# Schematic_Rev1.net
KiCad netlist of a schematic drawn in Altium Designer
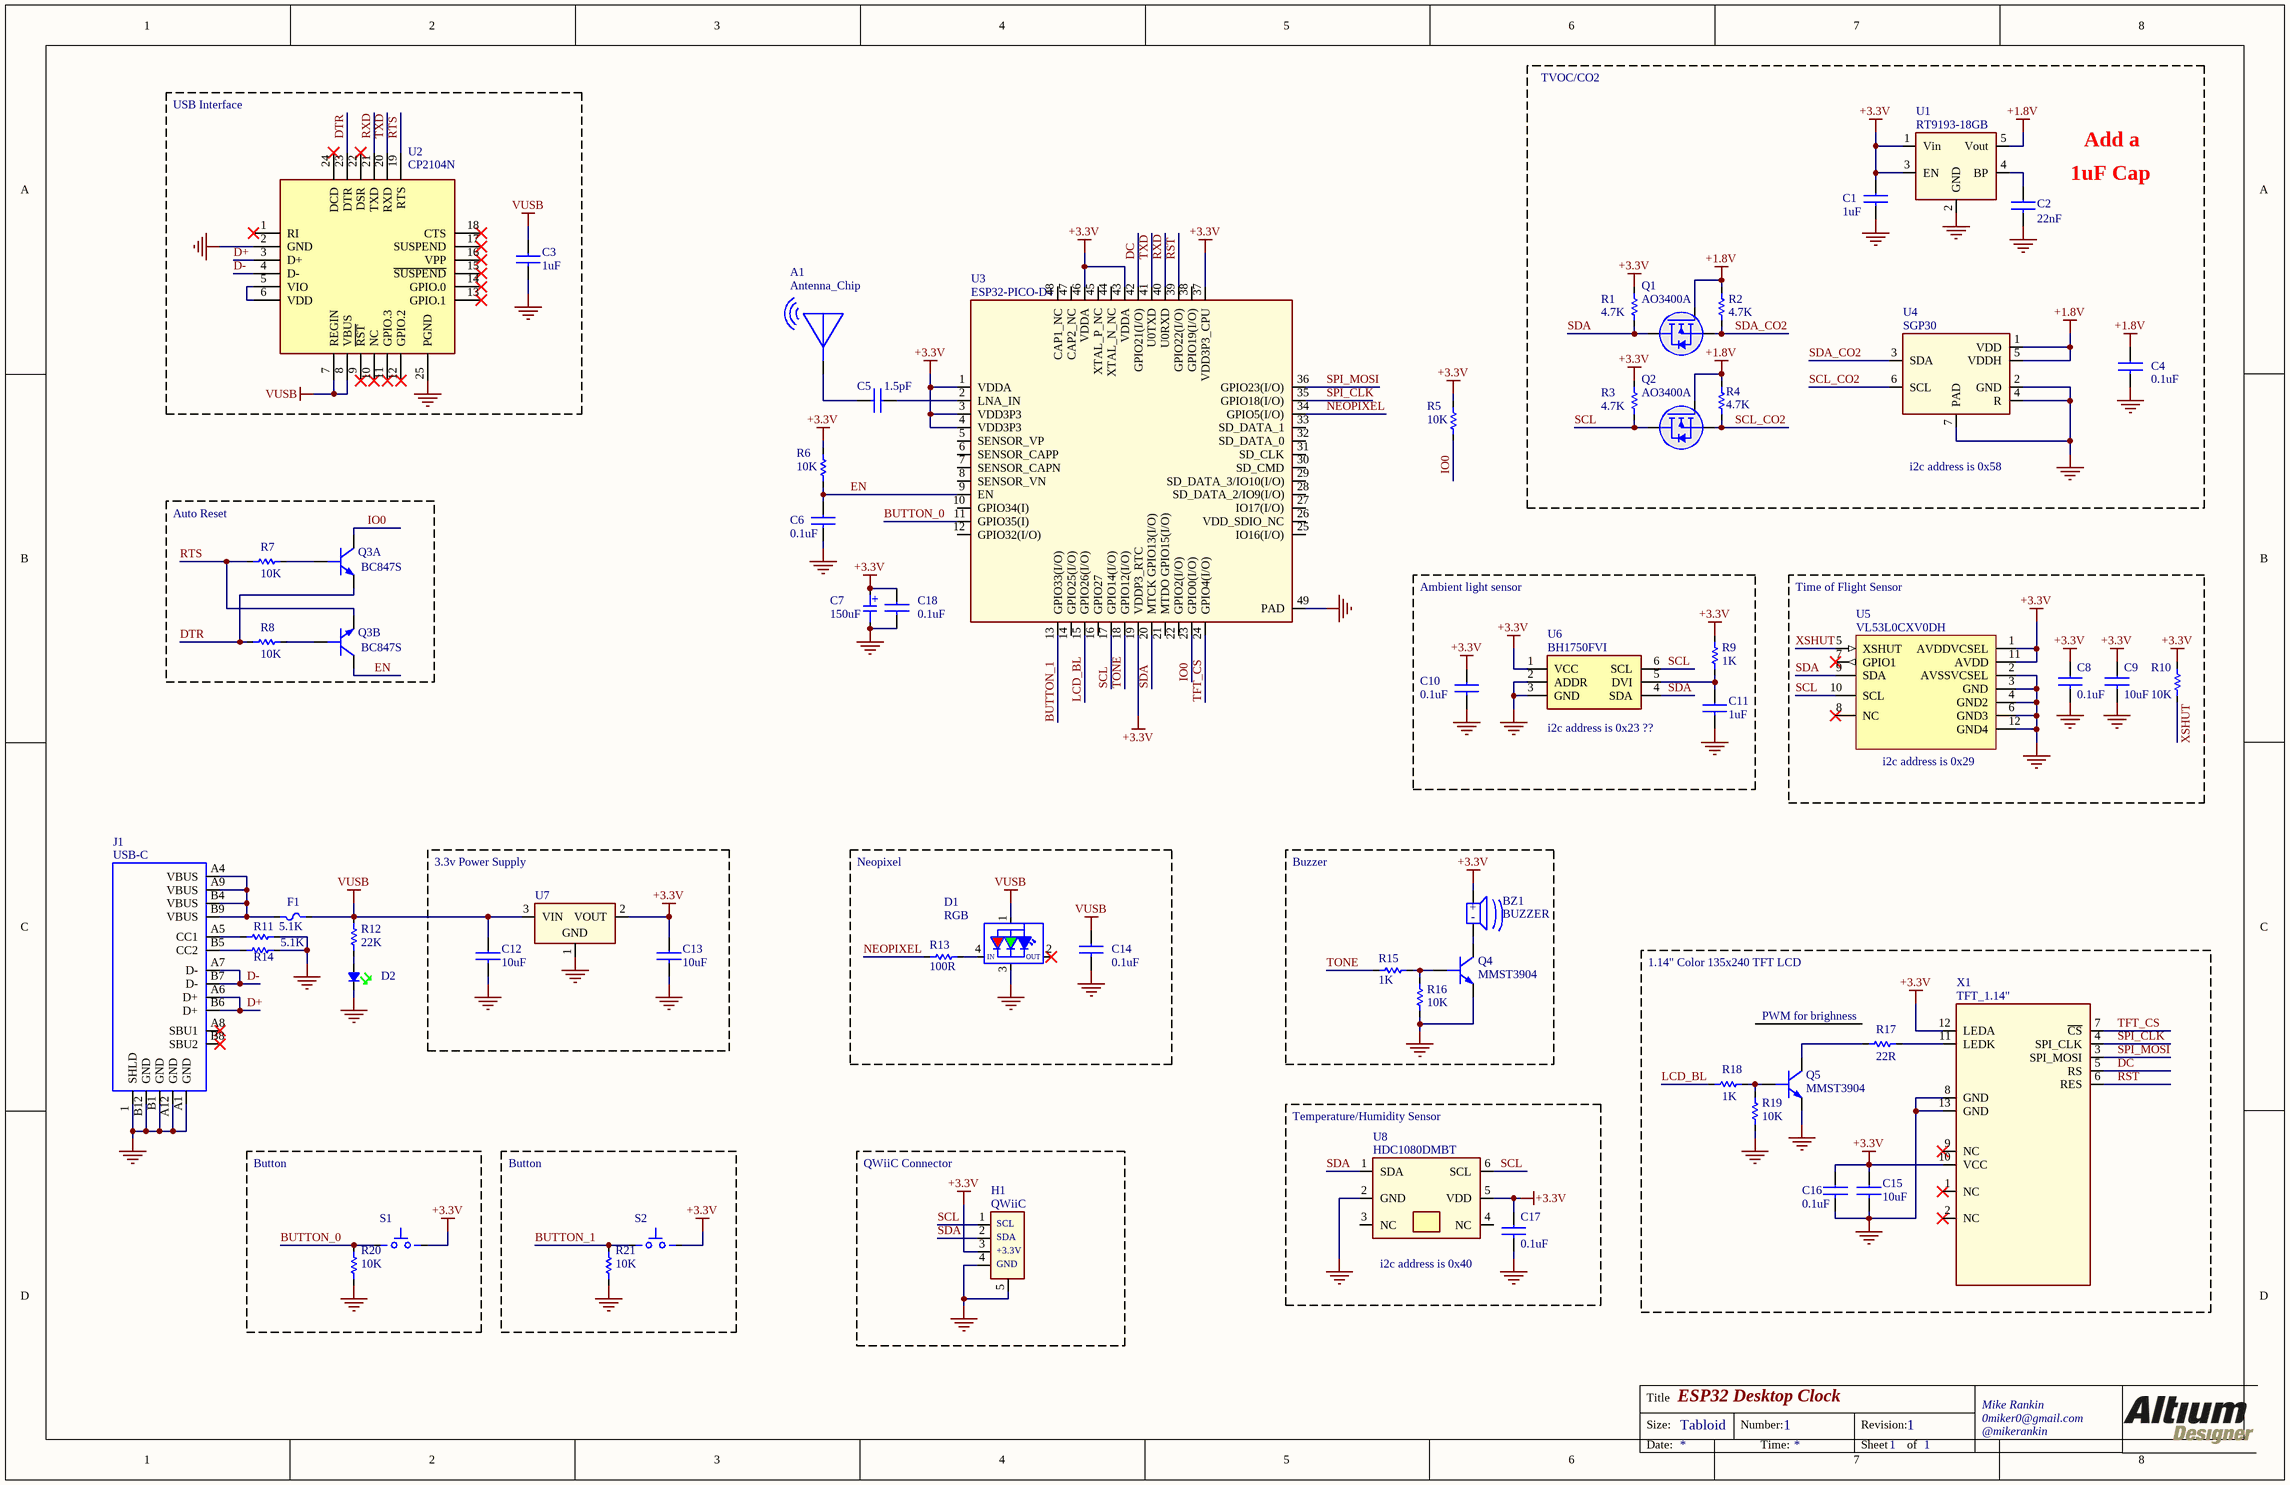
[diagram p0: Schematic_Rev1.SchDoc]

(export (version "E")
  (design (tool "Eeschema 10.0.6"))
  (components
    (comp (ref "A1")
      (value "Antenna_Chip")
      (footprint "AN9520-245")
      (description "Antenna Chip 2.4Gig")
      (fields (field (name "MANUFACTURER") "Rainsun") (field (name "PART_NUMBER") "C99665"))
      (libsource (lib "MAR") (part "Antenna_Chip"))
    )
    (comp (ref "BZ1")
      (value "BUZZER")
      (footprint "ST-025BH")
      (description "BUZZER MAGNETIC 2.7kHz Tone 2-4V SMD")
      (fields (field (name "PART_NUMBER") "ST-025BH") (field (name "MANUFACTURER") "SOBERTON"))
      (libsource (lib "MAR") (part "Buzzer_SMT"))
    )
    (comp (ref "C1")
      (value "1uF")
      (footprint "CAPC1005X56N")
      (description "CAP 1uF 0402")
      (libsource (lib "MAR") (part "CAP_0402"))
    )
    (comp (ref "C2")
      (value "22nF")
      (footprint "CAPC1005X56N")
      (description "CAP 22nF 0402")
      (libsource (lib "MAR") (part "CAP_0402"))
    )
    (comp (ref "C3")
      (value "1uF")
      (footprint "CAPC1005X56N")
      (description "CAP 1uF 16V 0402")
      (fields (field (name "PARTNUMBER") "C83063") (field (name "MANUFACTURER") "Walsin"))
      (libsource (lib "MAR") (part "CAP_0603"))
    )
    (comp (ref "C4")
      (value "0.1uF")
      (footprint "CAPC1005X56N")
      (description "CAP 0.1uF 0402")
      (libsource (lib "MAR") (part "CAP_0402"))
    )
    (comp (ref "C5")
      (value "1.5pF")
      (footprint "CAPC1005X56N")
      (description "CAP 1.5pF 0402")
      (fields (field (name "PART_NUMBER") "C147344") (field (name "MANUFACTURER") "Dafron"))
      (libsource (lib "MAR") (part "CAP_0402"))
    )
    (comp (ref "C6")
      (value "0.1uF")
      (footprint "CAPC1005X56N")
      (description "CAP 0.1uF 0402")
      (fields (field (name "PARTNUMBER") "C344190") (field (name "MANUFACTURER") "CCTC"))
      (libsource (lib "MAR") (part "CAP_0402"))
    )
    (comp (ref "C7")
      (value "150uF")
      (footprint "CAP_SM_CAN_0.250_DIA")
      (description "CAP 150uF, 10V SMT")
      (fields (field (name "PART_NUMBER") "C242018") (field (name "MANUFACTURER") "Suncon"))
      (libsource (lib "MAR") (part "CAP_ELEC_SMT"))
    )
    (comp (ref "C8")
      (value "0.1uF")
      (footprint "CAPC1005X56N")
      (description "CAP 0.1uF 0402")
      (fields (field (name "PARTNUMBER") "C344190") (field (name "MANUFACTURER") "CCTC"))
      (libsource (lib "MAR") (part "CAP_0402"))
    )
    (comp (ref "C9")
      (value "10uF")
      (footprint "CAPC2012X140N")
      (description "CAP 10uF 0805")
      (fields (field (name "MANUFACTURER") "Samsung") (field (name "PARTNUMBER") "C307520"))
      (libsource (lib "MAR") (part "CAP_0805"))
    )
    (comp (ref "C10")
      (value "0.1uF")
      (footprint "CAPC1005X56N")
      (description "CAP 0.1uF 0402")
      (libsource (lib "MAR") (part "CAP_0402"))
    )
    (comp (ref "C11")
      (value "1uF")
      (footprint "CAPC1005X56N")
      (description "CAP 1uF 16V 0402")
      (fields (field (name "PARTNUMBER") "C83063") (field (name "MANUFACTURER") "Walsin"))
      (libsource (lib "MAR") (part "CAP_0603"))
    )
    (comp (ref "C12")
      (value "10uF")
      (footprint "CAPC2012X140N")
      (description "CAP 10uF 16V 0805")
      (fields (field (name "PARTNUMBER") "C162317") (field (name "MANUFACTURER") "Murata"))
      (libsource (lib "MAR") (part "CAP_0805"))
    )
    (comp (ref "C13")
      (value "10uF")
      (footprint "CAPC2012X140N")
      (description "CAP 10uF 16V 0805")
      (fields (field (name "PARTNUMBER") "C162317") (field (name "MANUFACTURER") "Murata"))
      (libsource (lib "MAR") (part "CAP_0805"))
    )
    (comp (ref "C14")
      (value "0.1uF")
      (footprint "CAPC1005X56N")
      (description "CAP 0.1uF 0402")
      (libsource (lib "MAR") (part "CAP_0402"))
    )
    (comp (ref "C15")
      (value "10uF")
      (footprint "CAPC2012X140N")
      (description "CAP 10uF 0805")
      (fields (field (name "MANUFACTURER") "Samsung") (field (name "PARTNUMBER") "C307520"))
      (libsource (lib "MAR") (part "CAP_0805"))
    )
    (comp (ref "C16")
      (value "0.1uF")
      (footprint "CAPC1005X56N")
      (description "CAP 0.1uF 0402")
      (fields (field (name "PARTNUMBER") "C344190") (field (name "MANUFACTURER") "CCTC"))
      (libsource (lib "MAR") (part "CAP_0402"))
    )
    (comp (ref "C17")
      (value "0.1uF")
      (footprint "CAPC1005X56N")
      (description "CAP 0.1uF 0402")
      (fields (field (name "PARTNUMBER") "C344190") (field (name "MANUFACTURER") "CCTC"))
      (libsource (lib "MAR") (part "CAP_0402"))
    )
    (comp (ref "C18")
      (value "0.1uF")
      (footprint "CAPC1005X56N")
      (description "CAP 0.1uF 0402")
      (libsource (lib "MAR") (part "CAP_0402"))
    )
    (comp (ref "D1")
      (value "RGB")
      (footprint "SMD-5050")
      (description "LED,RGB,NEOPIXEL,WS2818")
      (fields (field (name "PART_NUMBER") "C139127") (field (name "MANUFACTURER") "Worldsemi"))
      (libsource (lib "MAR") (part "WS2812"))
    )
    (comp (ref "D2")
      (value "Green Led")
      (footprint "LED1005X40N-Green")
      (description "LED Green 0402")
      (fields (field (name "PART_NUMBER") "C74338"))
      (libsource (lib "MAR") (part "LED_0402_SMALL_GREEN"))
    )
    (comp (ref "F1")
      (value "TLC-PSMD050")
      (footprint "PTC2012X70L")
      (description "PTC FUSE 500mA hold, 1A trip 0805 SMD")
      (fields (field (name "MANUFACTURER") "TLC") (field (name "LCSC_PART_NUMBER") "C261942"))
      (libsource (lib "MAR") (part "PTC_FUSE"))
    )
    (comp (ref "H1")
      (value "QWiiC")
      (footprint "SM04B-SRSS-TB")
      (description "CONN HEADER 4POS .100 R/A QWIIC")
      (fields (field (name "MANUFACTURER") "JST") (field (name "PARTNUMBER") "SM04B-SRSS-TB(LF)(SN)"))
      (libsource (lib "MAR") (part "SM04B-SRSS-TB"))
    )
    (comp (ref "J1")
      (value "USB-C")
      (footprint "TYPE-C-31-M-12")
      (description "CONN RECPT USB-C")
      (fields (field (name "MANUFACTURER") "KHE") (field (name "PART_NUMBER") "C165948"))
      (libsource (lib "MAR") (part "USB-C"))
    )
    (comp (ref "Q1")
      (value "~")
      (footprint "SOT95P240X110-3N")
      (description "MOSFET N-CH 30V 35.7A SOT-23")
      (fields (field (name "MANUFACTURER") "Alpha & Omega") (field (name "PARTNUMBER") "AO3400A"))
      (libsource (lib "MAR") (part "AO3400A"))
    )
    (comp (ref "Q2")
      (value "~")
      (footprint "SOT95P240X110-3N")
      (description "MOSFET N-CH 30V 35.7A SOT-23")
      (fields (field (name "MANUFACTURER") "Alpha & Omega") (field (name "PARTNUMBER") "AO3400A"))
      (libsource (lib "MAR") (part "AO3400A"))
    )
    (comp (ref "Q3")
      (value "BC847S")
      (footprint "SOT65P210X110-6N")
      (description "TRANS 2NPN 44V 0.1A SC-70-6")
      (fields (field (name "MANUFACTURER") "Changjiang") (field (name "PARTNUMBER") "BC847S"))
      (libsource (lib "MAR") (part "BC847S"))
    )
    (comp (ref "Q4")
      (value "MMST3904")
      (footprint "SC-70")
      (description "TRANSISTOR NPN GP 40V SC-70")
      (fields (field (name "MANUFACTURER") "Changjiang") (field (name "PART_NUMBER") "C54879"))
      (libsource (lib "MAR") (part "MMST3904"))
    )
    (comp (ref "Q5")
      (value "MMST3904")
      (footprint "SC-70")
      (description "TRANSISTOR NPN GP 40V SC-70")
      (fields (field (name "MANUFACTURER") "Changjiang") (field (name "PART_NUMBER") "C54879"))
      (libsource (lib "MAR") (part "MMST3904"))
    )
    (comp (ref "R1")
      (value "4.7K")
      (footprint "RESC1005X40L (0402 FOOTPRINT)")
      (description "RES 4.7K 0402")
      (libsource (lib "MAR") (part "RES_0402"))
    )
    (comp (ref "R2")
      (value "4.7K")
      (footprint "RESC1005X40L (0402 FOOTPRINT)")
      (description "RES 4.7K 0402")
      (libsource (lib "MAR") (part "RES_0402"))
    )
    (comp (ref "R3")
      (value "4.7K")
      (footprint "RESC1005X40L (0402 FOOTPRINT)")
      (description "RES 4.7K 0402")
      (libsource (lib "MAR") (part "RES_0402"))
    )
    (comp (ref "R4")
      (value "4.7K")
      (footprint "RESC1005X40L (0402 FOOTPRINT)")
      (description "RES 4.7K 0402")
      (libsource (lib "MAR") (part "RES_0402"))
    )
    (comp (ref "R5")
      (value "10K")
      (footprint "RESC1005X40L (0402 FOOTPRINT)")
      (description "RES 10K 0402")
      (fields (field (name "PARTNUMBER") "C258091") (field (name "MANUFACTURER") "Guangdong"))
      (libsource (lib "MAR") (part "RES_0402"))
    )
    (comp (ref "R6")
      (value "10K")
      (footprint "RESC1005X40L (0402 FOOTPRINT)")
      (description "RES 10K 0402")
      (fields (field (name "PARTNUMBER") "C258091") (field (name "MANUFACTURER") "Guangdong"))
      (libsource (lib "MAR") (part "RES_0402"))
    )
    (comp (ref "R7")
      (value "10K")
      (footprint "RESC1005X40L (0402 FOOTPRINT)")
      (description "RES 10K 0402")
      (fields (field (name "PARTNUMBER") "C258091") (field (name "MANUFACTURER") "Guangdong"))
      (libsource (lib "MAR") (part "RES_0402"))
    )
    (comp (ref "R8")
      (value "10K")
      (footprint "RESC1005X40L (0402 FOOTPRINT)")
      (description "RES 10K 0402")
      (fields (field (name "PARTNUMBER") "C258091") (field (name "MANUFACTURER") "Guangdong"))
      (libsource (lib "MAR") (part "RES_0402"))
    )
    (comp (ref "R9")
      (value "1K")
      (footprint "RESC1005X40L (0402 FOOTPRINT)")
      (description "RES 1K 0402")
      (fields (field (name "PARTNUMBER") "C106235") (field (name "MANUFACTURER") "Yageo"))
      (libsource (lib "MAR") (part "RES_0402"))
    )
    (comp (ref "R10")
      (value "10K")
      (footprint "RESC1005X40L (0402 FOOTPRINT)")
      (description "RES 10K 0402")
      (fields (field (name "PARTNUMBER") "C258091") (field (name "MANUFACTURER") "Guangdong"))
      (libsource (lib "MAR") (part "RES_0402"))
    )
    (comp (ref "R11")
      (value "5.1K")
      (footprint "RESC1005X40L (0402 FOOTPRINT)")
      (description "RES 5.1K 0402")
      (libsource (lib "MAR") (part "RES_0603"))
    )
    (comp (ref "R12")
      (value "22K")
      (footprint "RESC1005X40L (0402 FOOTPRINT)")
      (description "RES 22K 0402")
      (fields (field (name "MANUFACTURER") "LIZ Elec") (field (name "PARTNUMBER") "C100310"))
      (libsource (lib "MAR") (part "RES_0603"))
    )
    (comp (ref "R13")
      (value "100R")
      (footprint "RESC1005X40L (0402 FOOTPRINT)")
      (description "RES 100R 0402")
      (fields (field (name "MANUFACTURER") "Yageo") (field (name "LCSC_PART_NUMBER") "C106232"))
      (libsource (lib "MAR") (part "RES_0603"))
    )
    (comp (ref "R14")
      (value "5.1K")
      (footprint "RESC1005X40L (0402 FOOTPRINT)")
      (description "RES 5.1K 0402")
      (libsource (lib "MAR") (part "RES_0603"))
    )
    (comp (ref "R15")
      (value "1K")
      (footprint "RESC1005X40L (0402 FOOTPRINT)")
      (description "RES 1K 0402")
      (libsource (lib "MAR") (part "RES_0402"))
    )
    (comp (ref "R16")
      (value "10K")
      (footprint "RESC1005X40L (0402 FOOTPRINT)")
      (description "RES 10K 0402")
      (fields (field (name "PARTNUMBER") "C258091") (field (name "MANUFACTURER") "Guangdong"))
      (libsource (lib "MAR") (part "RES_0402"))
    )
    (comp (ref "R17")
      (value "22R")
      (footprint "RESC1005X40L (0402 FOOTPRINT)")
      (description "RES 22R 0402")
      (fields (field (name "PARTNUMBER") "C25092") (field (name "MANUFACTURER") "Uniroyal"))
      (libsource (lib "MAR") (part "RES_0402"))
    )
    (comp (ref "R18")
      (value "1K")
      (footprint "RESC1005X40L (0402 FOOTPRINT)")
      (description "RES 1K 0402")
      (fields (field (name "PARTNUMBER") "C106235") (field (name "MANUFACTURER") "Yageo"))
      (libsource (lib "MAR") (part "RES_0402"))
    )
    (comp (ref "R19")
      (value "10K")
      (footprint "RESC1005X40L (0402 FOOTPRINT)")
      (description "RES 10K 0402")
      (fields (field (name "PARTNUMBER") "C258091") (field (name "MANUFACTURER") "Guangdong"))
      (libsource (lib "MAR") (part "RES_0402"))
    )
    (comp (ref "R20")
      (value "10K")
      (footprint "RESC1005X40L (0402 FOOTPRINT)")
      (description "RES 10K 0402")
      (fields (field (name "PART_NUMBER") "C258091") (field (name "MANUFACTURER") "Guangdong"))
      (libsource (lib "MAR") (part "RES_0402"))
    )
    (comp (ref "R21")
      (value "10K")
      (footprint "RESC1005X40L (0402 FOOTPRINT)")
      (description "RES 10K 0402")
      (fields (field (name "PART_NUMBER") "C258091") (field (name "MANUFACTURER") "Guangdong"))
      (libsource (lib "MAR") (part "RES_0402"))
    )
    (comp (ref "S1")
      (value "PushButton")
      (footprint "TSA063G70-250")
      (description "SWITCH TACTILE SPST-NO")
      (fields (field (name "PARTNUMBER") "C294567") (field (name "MANUFACTURER") "Bright"))
      (libsource (lib "MAR") (part "TSA063G70-250"))
    )
    (comp (ref "S2")
      (value "PushButton")
      (footprint "TSA063G70-250")
      (description "SWITCH TACTILE SPST-NO")
      (fields (field (name "PARTNUMBER") "C294567") (field (name "MANUFACTURER") "Bright"))
      (libsource (lib "MAR") (part "TSA063G70-250"))
    )
    (comp (ref "U1")
      (value "1.8V LDO")
      (footprint "SOT95P280X144-5N")
      (description "IC REG LDO 1.8V 300mA SOT23-5")
      (fields (field (name "MANUFACTURER") "Richtek USA") (field (name "PARTNUMBER") "RT9193-18GB"))
      (libsource (lib "MAR") (part "RT9193-18GB"))
    )
    (comp (ref "U2")
      (value "CP2104N")
      (footprint "24-QFN")
      (description "IC BRIDGE USB TO UART 24QFN")
      (fields (field (name "MANUFACTURER") "Silicon Labs") (field (name "PARTNUMBER") "C47742"))
      (libsource (lib "MAR") (part "CP2104N"))
    )
    (comp (ref "U3")
      (value "ESP32-PICO-D4")
      (footprint "QFN48_NEWEST 0.5mm pitch")
      (description "RF Transceiver ICs QFN-48_7x7x05P RoHS")
      (fields (field (name "MANUFACTURER") "Espressif") (field (name "PARTNUMBER") "C193707"))
      (libsource (lib "MAR") (part "ESP32-PICO-D4"))
    )
    (comp (ref "U4")
      (value "SGP30")
      (footprint "DFN-6 (2.45mm X 2.45mm)")
      (description "TVOC/CO2 Sensor")
      (fields (field (name "MANUFACTURER") "Sensirion AG") (field (name "PARTNUMBER") "SGP30-2.5K"))
      (libsource (lib "MAR") (part "SGP30"))
    )
    (comp (ref "U5")
      (value "VL53L0CXV0DH")
      (footprint "VL53L0CXV0DH")
      (description "LASER SENSOR")
      (fields (field (name "MANUFACTURER") "ST MICRO") (field (name "PARTNUMBER") "C91199"))
      (libsource (lib "MAR") (part "VL53L0CXV0DH"))
    )
    (comp (ref "U6")
      (value "BH1750FVI")
      (footprint "WSOF-6")
      (description "Optical Sensor Ambient I2C 6-SMD")
      (fields (field (name "MANUFACTURER") "Rohm") (field (name "PART_NUMBER") "C78960"))
      (libsource (lib "MAR") (part "BH1750FVI"))
    )
    (comp (ref "U7")
      (value "NCP1117LPST33T3G")
      (footprint "SOT230P700X180-4N")
      (description "IC REG LDO 3.3V 1A SOT223-3")
      (fields (field (name "MANUFACTURER") "ON Semi"))
      (libsource (lib "MAR") (part "NCP1117LPST33T3G"))
    )
    (comp (ref "U8")
      (value "HDC1080DMBT")
      (footprint "HDC1080")
      (description "Humidity/Temperature Sensor")
      (fields (field (name "MANUFACTURER") "Texas Instruments") (field (name "PARTNUMBER") "C82227"))
      (libsource (lib "MAR") (part "HDC1080DMBT"))
    )
    (comp (ref "X1")
      (value "TFT_1.14\"")
      (footprint "TFT_GLASS 1.14 INCH")
      (description "1.14 INCH TFT GLASS COLOR")
      (fields (field (name "PART_NUMBER") "ER-TFT1.14-1") (field (name "MANUFACTURER") "BuyDisplay"))
      (libsource (lib "MAR") (part "TFT_GLASS 1.14 INCH COLOR"))
    )
  )
  (nets
    (net (code "1") (name "+1.8V") (class "Default")
      (node (ref "C4") (pin "1") (pinfunction "1_1") (pintype "passive"))
      (node (ref "Q1") (pin "1") (pinfunction "G_1") (pintype "passive"))
      (node (ref "Q2") (pin "1") (pinfunction "G_1") (pintype "passive"))
      (node (ref "R2") (pin "2") (pintype "passive"))
      (node (ref "R4") (pin "2") (pintype "passive"))
      (node (ref "U1") (pin "5") (pinfunction "Vout_5") (pintype "passive"))
      (node (ref "U4") (pin "1") (pinfunction "VDD_1") (pintype "power_in"))
      (node (ref "U4") (pin "5") (pinfunction "VDDH_5") (pintype "power_in"))
    )
    (net (code "2") (name "+3.3V") (class "Default")
      (node (ref "BZ1") (pin "1") (pinfunction "1_1") (pintype "passive"))
      (node (ref "C1") (pin "1") (pinfunction "1_1") (pintype "passive"))
      (node (ref "C10") (pin "1") (pinfunction "1_1") (pintype "passive"))
      (node (ref "C13") (pin "1") (pinfunction "1_1") (pintype "passive"))
      (node (ref "C15") (pin "1") (pinfunction "1_1") (pintype "passive"))
      (node (ref "C16") (pin "1") (pinfunction "1_1") (pintype "passive"))
      (node (ref "C17") (pin "1") (pinfunction "1_1") (pintype "passive"))
      (node (ref "C18") (pin "1") (pinfunction "1_1") (pintype "passive"))
      (node (ref "C7") (pin "1") (pintype "passive"))
      (node (ref "C8") (pin "1") (pinfunction "1_1") (pintype "passive"))
      (node (ref "C9") (pin "1") (pinfunction "1_1") (pintype "passive"))
      (node (ref "H1") (pin "3") (pintype "passive"))
      (node (ref "R1") (pin "2") (pintype "passive"))
      (node (ref "R10") (pin "1") (pintype "passive"))
      (node (ref "R3") (pin "2") (pintype "passive"))
      (node (ref "R5") (pin "1") (pintype "passive"))
      (node (ref "R6") (pin "1") (pintype "passive"))
      (node (ref "R9") (pin "2") (pintype "passive"))
      (node (ref "S1") (pin "2") (pinfunction "B_2") (pintype "passive"))
      (node (ref "S2") (pin "2") (pinfunction "B_2") (pintype "passive"))
      (node (ref "U1") (pin "1") (pinfunction "Vin_1") (pintype "passive"))
      (node (ref "U1") (pin "3") (pinfunction "EN_3") (pintype "passive"))
      (node (ref "U3") (pin "1") (pinfunction "VDDA_1") (pintype "power_in"))
      (node (ref "U3") (pin "19") (pinfunction "VDDP3_RTC_19") (pintype "passive"))
      (node (ref "U3") (pin "3") (pinfunction "VDD3P3_3") (pintype "power_in"))
      (node (ref "U3") (pin "37") (pinfunction "VDD3P3_CPU_37") (pintype "power_in"))
      (node (ref "U3") (pin "4") (pinfunction "VDD3P3_4") (pintype "power_in"))
      (node (ref "U3") (pin "43") (pinfunction "VDDA_43") (pintype "power_in"))
      (node (ref "U3") (pin "46") (pinfunction "VDDA_46") (pintype "power_in"))
      (node (ref "U5") (pin "1") (pinfunction "AVDDVCSEL_1") (pintype "power_in"))
      (node (ref "U5") (pin "11") (pinfunction "AVDD_11") (pintype "power_in"))
      (node (ref "U6") (pin "1") (pinfunction "VCC_1") (pintype "power_in"))
      (node (ref "U7") (pin "2") (pinfunction "VOUT_2") (pintype "power_in"))
      (node (ref "U8") (pin "5") (pinfunction "VDD_5") (pintype "power_in"))
      (node (ref "X1") (pin "10") (pinfunction "VCC_10") (pintype "power_in"))
      (node (ref "X1") (pin "12") (pinfunction "LEDA_12") (pintype "passive"))
    )
    (net (code "4") (name "/BUTTON_0") (class "Default")
      (node (ref "R20") (pin "1") (pintype "passive"))
      (node (ref "S1") (pin "1") (pinfunction "A_1") (pintype "passive"))
      (node (ref "U3") (pin "11") (pinfunction "GPIO35(I)_11") (pintype "passive"))
    )
    (net (code "5") (name "/BUTTON_1") (class "Default")
      (node (ref "R21") (pin "1") (pintype "passive"))
      (node (ref "S2") (pin "1") (pinfunction "A_1") (pintype "passive"))
      (node (ref "U3") (pin "13") (pinfunction "GPIO33(I/O)_13") (pintype "passive"))
    )
    (net (code "6") (name "/D+") (class "Default")
      (node (ref "J1") (pin "A6") (pinfunction "D+_A6") (pintype "power_in"))
      (node (ref "J1") (pin "B6") (pinfunction "D+_B6") (pintype "power_in"))
      (node (ref "U2") (pin "3") (pinfunction "D+_3") (pintype "passive"))
    )
    (net (code "7") (name "/D-") (class "Default")
      (node (ref "J1") (pin "A7") (pinfunction "D-_A7") (pintype "power_in"))
      (node (ref "J1") (pin "B7") (pinfunction "D-_B7") (pintype "power_in"))
      (node (ref "U2") (pin "4") (pinfunction "D-_4") (pintype "passive"))
    )
    (net (code "8") (name "/DC") (class "Default")
      (node (ref "U3") (pin "42") (pinfunction "GPIO21(I/O)_42") (pintype "passive"))
      (node (ref "X1") (pin "5") (pinfunction "RS_5") (pintype "passive"))
    )
    (net (code "9") (name "/DTR") (class "Default")
      (node (ref "Q3") (pin "1") (pinfunction "E1_1") (pintype "passive"))
      (node (ref "R8") (pin "2") (pintype "passive"))
      (node (ref "U2") (pin "23") (pinfunction "DTR_23") (pintype "passive"))
    )
    (net (code "10") (name "/EN") (class "Default")
      (node (ref "C6") (pin "1") (pinfunction "1_1") (pintype "passive"))
      (node (ref "Q3") (pin "3") (pinfunction "C2_3") (pintype "passive"))
      (node (ref "R6") (pin "2") (pintype "passive"))
      (node (ref "U3") (pin "9") (pinfunction "EN_9") (pintype "passive"))
    )
    (net (code "11") (name "/IO0") (class "Default")
      (node (ref "Q3") (pin "6") (pinfunction "C1_6") (pintype "passive"))
      (node (ref "R5") (pin "2") (pintype "passive"))
      (node (ref "U3") (pin "23") (pinfunction "GPIO0(I/O)_23") (pintype "passive"))
    )
    (net (code "12") (name "/LCD_BL") (class "Default")
      (node (ref "R18") (pin "1") (pintype "passive"))
      (node (ref "U3") (pin "15") (pinfunction "GPIO26(I/O)_15") (pintype "passive"))
    )
    (net (code "13") (name "/NEOPIXEL") (class "Default")
      (node (ref "R13") (pin "2") (pintype "passive"))
      (node (ref "U3") (pin "34") (pinfunction "GPIO5(I/O)_34") (pintype "passive"))
    )
    (net (code "14") (name "/RST") (class "Default")
      (node (ref "U3") (pin "39") (pinfunction "GPIO22(I/O)_39") (pintype "passive"))
      (node (ref "X1") (pin "6") (pinfunction "RES_6") (pintype "passive"))
    )
    (net (code "15") (name "/RTS") (class "Default")
      (node (ref "Q3") (pin "4") (pinfunction "E2_4") (pintype "passive"))
      (node (ref "R7") (pin "2") (pintype "passive"))
      (node (ref "U2") (pin "19") (pinfunction "RTS_19") (pintype "passive"))
    )
    (net (code "16") (name "/RXD") (class "Default")
      (node (ref "U2") (pin "21") (pinfunction "TXD_21") (pintype "passive"))
      (node (ref "U3") (pin "40") (pinfunction "U0RXD_40") (pintype "passive"))
    )
    (net (code "17") (name "/SCL") (class "Default")
      (node (ref "H1") (pin "1") (pintype "passive"))
      (node (ref "Q2") (pin "3") (pinfunction "D_3") (pintype "passive"))
      (node (ref "R3") (pin "1") (pintype "passive"))
      (node (ref "U3") (pin "17") (pinfunction "GPIO14(I/O)_17") (pintype "passive"))
      (node (ref "U5") (pin "10") (pinfunction "SCL_10") (pintype "passive"))
      (node (ref "U6") (pin "6") (pinfunction "SCL_6") (pintype "passive"))
      (node (ref "U8") (pin "6") (pinfunction "SCL_6") (pintype "passive"))
    )
    (net (code "18") (name "/SCL_CO2") (class "Default")
      (node (ref "Q2") (pin "2") (pinfunction "S_2") (pintype "passive"))
      (node (ref "R4") (pin "1") (pintype "passive"))
      (node (ref "U4") (pin "6") (pinfunction "SCL_6") (pintype "passive"))
    )
    (net (code "19") (name "/SDA") (class "Default")
      (node (ref "H1") (pin "2") (pintype "passive"))
      (node (ref "Q1") (pin "3") (pinfunction "D_3") (pintype "passive"))
      (node (ref "R1") (pin "1") (pintype "passive"))
      (node (ref "U3") (pin "20") (pinfunction "MTCK_GPIO13(I/O)_20") (pintype "passive"))
      (node (ref "U5") (pin "9") (pinfunction "SDA_9") (pintype "passive"))
      (node (ref "U6") (pin "4") (pinfunction "SDA_4") (pintype "passive"))
      (node (ref "U8") (pin "1") (pinfunction "SDA_1") (pintype "passive"))
    )
    (net (code "20") (name "/SDA_CO2") (class "Default")
      (node (ref "Q1") (pin "2") (pinfunction "S_2") (pintype "passive"))
      (node (ref "R2") (pin "1") (pintype "passive"))
      (node (ref "U4") (pin "3") (pinfunction "SDA_3") (pintype "passive"))
    )
    (net (code "21") (name "/SPI_CLK") (class "Default")
      (node (ref "U3") (pin "35") (pinfunction "GPIO18(I/O)_35") (pintype "passive"))
      (node (ref "X1") (pin "4") (pinfunction "SPI_CLK_4") (pintype "passive"))
    )
    (net (code "22") (name "/SPI_MOSI") (class "Default")
      (node (ref "U3") (pin "36") (pinfunction "GPIO23(I/O)_36") (pintype "passive"))
      (node (ref "X1") (pin "3") (pinfunction "SPI_MOSI_3") (pintype "passive"))
    )
    (net (code "23") (name "/TFT_CS") (class "Default")
      (node (ref "U3") (pin "24") (pinfunction "GPIO4(I/O)_24") (pintype "passive"))
      (node (ref "X1") (pin "7") (pinfunction "~{CS}_7") (pintype "passive"))
    )
    (net (code "24") (name "/TONE") (class "Default")
      (node (ref "R15") (pin "2") (pintype "passive"))
      (node (ref "U3") (pin "18") (pinfunction "GPIO12(I/O)_18") (pintype "passive"))
    )
    (net (code "25") (name "/TXD") (class "Default")
      (node (ref "U2") (pin "20") (pinfunction "RXD_20") (pintype "passive"))
      (node (ref "U3") (pin "41") (pinfunction "U0TXD_41") (pintype "passive"))
    )
    (net (code "26") (name "/XSHUT") (class "Default")
      (node (ref "R10") (pin "2") (pintype "passive"))
      (node (ref "U5") (pin "5") (pinfunction "XSHUT_5") (pintype "input"))
    )
    (net (code "27") (name "GND") (class "Default")
      (node (ref "C1") (pin "2") (pinfunction "2_2") (pintype "passive"))
      (node (ref "C10") (pin "2") (pinfunction "2_2") (pintype "passive"))
      (node (ref "C11") (pin "2") (pinfunction "2_2") (pintype "passive"))
      (node (ref "C12") (pin "2") (pinfunction "2_2") (pintype "passive"))
      (node (ref "C13") (pin "2") (pinfunction "2_2") (pintype "passive"))
      (node (ref "C14") (pin "2") (pinfunction "2_2") (pintype "passive"))
      (node (ref "C15") (pin "2") (pinfunction "2_2") (pintype "passive"))
      (node (ref "C16") (pin "2") (pinfunction "2_2") (pintype "passive"))
      (node (ref "C17") (pin "2") (pinfunction "2_2") (pintype "passive"))
      (node (ref "C18") (pin "2") (pinfunction "2_2") (pintype "passive"))
      (node (ref "C2") (pin "2") (pinfunction "2_2") (pintype "passive"))
      (node (ref "C3") (pin "2") (pinfunction "2_2") (pintype "passive"))
      (node (ref "C4") (pin "2") (pinfunction "2_2") (pintype "passive"))
      (node (ref "C6") (pin "2") (pinfunction "2_2") (pintype "passive"))
      (node (ref "C7") (pin "2") (pintype "passive"))
      (node (ref "C8") (pin "2") (pinfunction "2_2") (pintype "passive"))
      (node (ref "C9") (pin "2") (pinfunction "2_2") (pintype "passive"))
      (node (ref "D1") (pin "3") (pintype "passive"))
      (node (ref "D2") (pin "1") (pintype "passive"))
      (node (ref "H1") (pin "4") (pintype "passive"))
      (node (ref "H1") (pin "5") (pintype "passive"))
      (node (ref "J1") (pin "1") (pinfunction "SHLD_1") (pintype "power_in"))
      (node (ref "J1") (pin "A1") (pinfunction "GND_A1") (pintype "power_in"))
      (node (ref "J1") (pin "A12") (pinfunction "GND_A12") (pintype "power_in"))
      (node (ref "J1") (pin "B1") (pinfunction "GND_B1") (pintype "power_in"))
      (node (ref "J1") (pin "B12") (pinfunction "GND_B12") (pintype "passive"))
      (node (ref "Q4") (pin "2") (pinfunction "E_2") (pintype "passive"))
      (node (ref "Q5") (pin "2") (pinfunction "E_2") (pintype "passive"))
      (node (ref "R11") (pin "2") (pintype "passive"))
      (node (ref "R14") (pin "2") (pintype "passive"))
      (node (ref "R16") (pin "2") (pintype "passive"))
      (node (ref "R19") (pin "2") (pintype "passive"))
      (node (ref "R20") (pin "2") (pintype "passive"))
      (node (ref "R21") (pin "2") (pintype "passive"))
      (node (ref "U1") (pin "2") (pinfunction "GND_2") (pintype "power_in"))
      (node (ref "U2") (pin "2") (pinfunction "GND_2") (pintype "power_in"))
      (node (ref "U2") (pin "25") (pinfunction "PGND_25") (pintype "passive"))
      (node (ref "U3") (pin "49") (pinfunction "PAD_49") (pintype "power_in"))
      (node (ref "U4") (pin "2") (pinfunction "GND_2") (pintype "power_in"))
      (node (ref "U4") (pin "4") (pinfunction "R_4") (pintype "passive"))
      (node (ref "U4") (pin "7") (pinfunction "PAD_7") (pintype "passive"))
      (node (ref "U5") (pin "12") (pinfunction "GND4_12") (pintype "power_in"))
      (node (ref "U5") (pin "2") (pinfunction "AVSSVCSEL_2") (pintype "power_in"))
      (node (ref "U5") (pin "3") (pinfunction "GND_3") (pintype "power_in"))
      (node (ref "U5") (pin "4") (pinfunction "GND2_4") (pintype "power_in"))
      (node (ref "U5") (pin "6") (pinfunction "GND3_6") (pintype "power_in"))
      (node (ref "U6") (pin "2") (pinfunction "ADDR_2") (pintype "passive"))
      (node (ref "U6") (pin "3") (pinfunction "GND_3") (pintype "power_in"))
      (node (ref "U7") (pin "1") (pinfunction "GND_1") (pintype "power_in"))
      (node (ref "U8") (pin "2") (pinfunction "GND_2") (pintype "power_in"))
      (node (ref "X1") (pin "13") (pinfunction "GND_13") (pintype "power_in"))
      (node (ref "X1") (pin "8") (pinfunction "GND_8") (pintype "power_in"))
    )
    (net (code "28") (name "Net-(A1-Pad1)") (class "Default")
      (node (ref "A1") (pin "1") (pintype "passive"))
      (node (ref "C5") (pin "2") (pinfunction "2_2") (pintype "passive"))
    )
    (net (code "29") (name "Net-(D1-Pad4)") (class "Default")
      (node (ref "D1") (pin "4") (pintype "passive"))
      (node (ref "R13") (pin "1") (pintype "passive"))
    )
    (net (code "30") (name "Net-(D2-Pad2)") (class "Default")
      (node (ref "D2") (pin "2") (pintype "passive"))
      (node (ref "R12") (pin "1") (pintype "passive"))
    )
    (net (code "31") (name "Net-(F1-Pad2)") (class "Default")
      (node (ref "F1") (pin "2") (pintype "passive"))
      (node (ref "J1") (pin "A4") (pinfunction "VBUS_A4") (pintype "passive"))
      (node (ref "J1") (pin "A9") (pinfunction "VBUS_A9") (pintype "power_in"))
      (node (ref "J1") (pin "B4") (pinfunction "VBUS_B4") (pintype "power_in"))
      (node (ref "J1") (pin "B9") (pinfunction "VBUS_B9") (pintype "passive"))
    )
    (net (code "32") (name "Net-(J1-CC1)") (class "Default")
      (node (ref "J1") (pin "A5") (pinfunction "CC1_A5") (pintype "power_in"))
      (node (ref "R11") (pin "1") (pintype "passive"))
    )
    (net (code "33") (name "Net-(J1-CC2)") (class "Default")
      (node (ref "J1") (pin "B5") (pinfunction "CC2_B5") (pintype "power_in"))
      (node (ref "R14") (pin "1") (pintype "passive"))
    )
    (net (code "34") (name "Net-(Q3A-B1)") (class "Default")
      (node (ref "Q3") (pin "2") (pinfunction "B1_2") (pintype "passive"))
      (node (ref "R7") (pin "1") (pintype "passive"))
    )
    (net (code "35") (name "Net-(Q3B-B2)") (class "Default")
      (node (ref "Q3") (pin "5") (pinfunction "B2_5") (pintype "passive"))
      (node (ref "R8") (pin "1") (pintype "passive"))
    )
    (net (code "36") (name "Net-(Q4-B)") (class "Default")
      (node (ref "Q4") (pin "1") (pinfunction "B_1") (pintype "passive"))
      (node (ref "R15") (pin "1") (pintype "passive"))
      (node (ref "R16") (pin "1") (pintype "passive"))
    )
    (net (code "37") (name "Net-(Q4-C)") (class "Default")
      (node (ref "BZ1") (pin "2") (pinfunction "2_2") (pintype "passive"))
      (node (ref "Q4") (pin "3") (pinfunction "C_3") (pintype "passive"))
    )
    (net (code "38") (name "Net-(Q5-B)") (class "Default")
      (node (ref "Q5") (pin "1") (pinfunction "B_1") (pintype "passive"))
      (node (ref "R18") (pin "2") (pintype "passive"))
      (node (ref "R19") (pin "1") (pintype "passive"))
    )
    (net (code "39") (name "Net-(Q5-C)") (class "Default")
      (node (ref "Q5") (pin "3") (pinfunction "C_3") (pintype "passive"))
      (node (ref "R17") (pin "2") (pintype "passive"))
    )
    (net (code "40") (name "Net-(U1-BP)") (class "Default")
      (node (ref "C2") (pin "1") (pinfunction "1_1") (pintype "passive"))
      (node (ref "U1") (pin "4") (pinfunction "BP_4") (pintype "passive"))
    )
    (net (code "41") (name "Net-(U2-VDD)") (class "Default")
      (node (ref "U2") (pin "5") (pinfunction "VIO_5") (pintype "power_in"))
      (node (ref "U2") (pin "6") (pinfunction "VDD_6") (pintype "power_in"))
    )
    (net (code "42") (name "Net-(U3-LNA_IN)") (class "Default")
      (node (ref "C5") (pin "1") (pinfunction "1_1") (pintype "passive"))
      (node (ref "U3") (pin "2") (pinfunction "LNA_IN_2") (pintype "passive"))
    )
    (net (code "43") (name "Net-(U6-DVI)") (class "Default")
      (node (ref "C11") (pin "1") (pinfunction "1_1") (pintype "passive"))
      (node (ref "R9") (pin "1") (pintype "passive"))
      (node (ref "U6") (pin "5") (pinfunction "DVI_5") (pintype "passive"))
    )
    (net (code "44") (name "Net-(X1-LEDK)") (class "Default")
      (node (ref "R17") (pin "1") (pintype "passive"))
      (node (ref "X1") (pin "11") (pinfunction "LEDK_11") (pintype "passive"))
    )
    (net (code "45") (name "VUSB") (class "Default")
      (node (ref "C12") (pin "1") (pinfunction "1_1") (pintype "passive"))
      (node (ref "C14") (pin "1") (pinfunction "1_1") (pintype "passive"))
      (node (ref "C3") (pin "1") (pinfunction "1_1") (pintype "passive"))
      (node (ref "D1") (pin "1") (pintype "passive"))
      (node (ref "F1") (pin "1") (pintype "passive"))
      (node (ref "R12") (pin "2") (pintype "passive"))
      (node (ref "U2") (pin "7") (pinfunction "REGIN_7") (pintype "power_in"))
      (node (ref "U2") (pin "8") (pinfunction "VBUS_8") (pintype "power_in"))
      (node (ref "U7") (pin "3") (pinfunction "VIN_3") (pintype "power_in"))
    )
    (net (code "46") (name "unconnected-(D1-DIN-Pad2)") (class "Default")
      (node (ref "D1") (pin "2") (pinfunction "DIN_2") (pintype "passive+no_connect"))
    )
    (net (code "47") (name "unconnected-(J1-SBU1-PadA8)") (class "Default")
      (node (ref "J1") (pin "A8") (pinfunction "SBU1_A8") (pintype "power_in+no_connect"))
    )
    (net (code "48") (name "unconnected-(J1-SBU2-PadB8)") (class "Default")
      (node (ref "J1") (pin "B8") (pinfunction "SBU2_B8") (pintype "power_in+no_connect"))
    )
    (net (code "49") (name "unconnected-(U2-CTS-Pad18)") (class "Default")
      (node (ref "U2") (pin "18") (pinfunction "CTS_18") (pintype "passive+no_connect"))
    )
    (net (code "50") (name "unconnected-(U2-DCD-Pad24)") (class "Default")
      (node (ref "U2") (pin "24") (pinfunction "DCD_24") (pintype "passive+no_connect"))
    )
    (net (code "51") (name "unconnected-(U2-DSR-Pad22)") (class "Default")
      (node (ref "U2") (pin "22") (pinfunction "DSR_22") (pintype "passive+no_connect"))
    )
    (net (code "52") (name "unconnected-(U2-GPIO.0-Pad14)") (class "Default")
      (node (ref "U2") (pin "14") (pinfunction "GPIO.0_14") (pintype "passive+no_connect"))
    )
    (net (code "53") (name "unconnected-(U2-GPIO.1-Pad13)") (class "Default")
      (node (ref "U2") (pin "13") (pinfunction "GPIO.1_13") (pintype "passive+no_connect"))
    )
    (net (code "54") (name "unconnected-(U2-GPIO.2-Pad12)") (class "Default")
      (node (ref "U2") (pin "12") (pinfunction "GPIO.2_12") (pintype "passive+no_connect"))
    )
    (net (code "55") (name "unconnected-(U2-GPIO.3-Pad11)") (class "Default")
      (node (ref "U2") (pin "11") (pinfunction "GPIO.3_11") (pintype "passive+no_connect"))
    )
    (net (code "56") (name "unconnected-(U2-NC-Pad10)") (class "Default")
      (node (ref "U2") (pin "10") (pinfunction "NC_10") (pintype "passive+no_connect"))
    )
    (net (code "57") (name "unconnected-(U2-RI-Pad1)") (class "Default")
      (node (ref "U2") (pin "1") (pinfunction "RI_1") (pintype "passive+no_connect"))
    )
    (net (code "58") (name "unconnected-(U2-SUSPEND-Pad17)") (class "Default")
      (node (ref "U2") (pin "17") (pinfunction "SUSPEND_17") (pintype "passive+no_connect"))
    )
    (net (code "59") (name "unconnected-(U2-VPP-Pad16)") (class "Default")
      (node (ref "U2") (pin "16") (pinfunction "VPP_16") (pintype "passive+no_connect"))
    )
    (net (code "60") (name "unconnected-(U2-~{RST}-Pad9)") (class "Default")
      (node (ref "U2") (pin "9") (pinfunction "~{RST}_9") (pintype "passive+no_connect"))
    )
    (net (code "61") (name "unconnected-(U2-~{SUSPEND}-Pad15)") (class "Default")
      (node (ref "U2") (pin "15") (pinfunction "~{SUSPEND}_15") (pintype "passive+no_connect"))
    )
    (net (code "62") (name "unconnected-(U3-CAP1_NC-Pad48)") (class "Default")
      (node (ref "U3") (pin "48") (pinfunction "CAP1_NC_48") (pintype "passive"))
    )
    (net (code "63") (name "unconnected-(U3-CAP2_NC-Pad47)") (class "Default")
      (node (ref "U3") (pin "47") (pinfunction "CAP2_NC_47") (pintype "passive"))
    )
    (net (code "64") (name "unconnected-(U3-GPIO2(I{slash}O)-Pad22)") (class "Default")
      (node (ref "U3") (pin "22") (pinfunction "GPIO2(I/O)_22") (pintype "passive"))
    )
    (net (code "65") (name "unconnected-(U3-GPIO19(I{slash}O)-Pad38)") (class "Default")
      (node (ref "U3") (pin "38") (pinfunction "GPIO19(I/O)_38") (pintype "passive"))
    )
    (net (code "66") (name "unconnected-(U3-GPIO25(I{slash}O)-Pad14)") (class "Default")
      (node (ref "U3") (pin "14") (pinfunction "GPIO25(I/O)_14") (pintype "passive"))
    )
    (net (code "67") (name "unconnected-(U3-GPIO27-Pad16)") (class "Default")
      (node (ref "U3") (pin "16") (pinfunction "GPIO27_16") (pintype "passive"))
    )
    (net (code "68") (name "unconnected-(U3-GPIO32(I{slash}O)-Pad12)") (class "Default")
      (node (ref "U3") (pin "12") (pinfunction "GPIO32(I/O)_12") (pintype "passive"))
    )
    (net (code "69") (name "unconnected-(U3-GPIO34(I)-Pad10)") (class "Default")
      (node (ref "U3") (pin "10") (pinfunction "GPIO34(I)_10") (pintype "passive"))
    )
    (net (code "70") (name "unconnected-(U3-IO16(I{slash}O)-Pad25)") (class "Default")
      (node (ref "U3") (pin "25") (pinfunction "IO16(I/O)_25") (pintype "passive"))
    )
    (net (code "71") (name "unconnected-(U3-IO17(I{slash}O)-Pad27)") (class "Default")
      (node (ref "U3") (pin "27") (pinfunction "IO17(I/O)_27") (pintype "passive"))
    )
    (net (code "72") (name "unconnected-(U3-MTDO_GPIO15(I{slash}O)-Pad21)") (class "Default")
      (node (ref "U3") (pin "21") (pinfunction "MTDO_GPIO15(I/O)_21") (pintype "passive"))
    )
    (net (code "73") (name "unconnected-(U3-SD_CLK-Pad31)") (class "Default")
      (node (ref "U3") (pin "31") (pinfunction "SD_CLK_31") (pintype "passive"))
    )
    (net (code "74") (name "unconnected-(U3-SD_CMD-Pad30)") (class "Default")
      (node (ref "U3") (pin "30") (pinfunction "SD_CMD_30") (pintype "passive"))
    )
    (net (code "75") (name "unconnected-(U3-SD_DATA_0-Pad32)") (class "Default")
      (node (ref "U3") (pin "32") (pinfunction "SD_DATA_0_32") (pintype "passive"))
    )
    (net (code "76") (name "unconnected-(U3-SD_DATA_1-Pad33)") (class "Default")
      (node (ref "U3") (pin "33") (pinfunction "SD_DATA_1_33") (pintype "passive"))
    )
    (net (code "77") (name "unconnected-(U3-SD_DATA_2{slash}IO9(I{slash}O)-Pad28)") (class "Default")
      (node (ref "U3") (pin "28") (pinfunction "SD_DATA_2/IO9(I/O)_28") (pintype "passive"))
    )
    (net (code "78") (name "unconnected-(U3-SD_DATA_3{slash}IO10(I{slash}O)-Pad29)") (class "Default")
      (node (ref "U3") (pin "29") (pinfunction "SD_DATA_3/IO10(I/O)_29") (pintype "passive"))
    )
    (net (code "79") (name "unconnected-(U3-SENSOR_CAPN-Pad7)") (class "Default")
      (node (ref "U3") (pin "7") (pinfunction "SENSOR_CAPN_7") (pintype "passive"))
    )
    (net (code "80") (name "unconnected-(U3-SENSOR_CAPP-Pad6)") (class "Default")
      (node (ref "U3") (pin "6") (pinfunction "SENSOR_CAPP_6") (pintype "passive"))
    )
    (net (code "81") (name "unconnected-(U3-SENSOR_VN-Pad8)") (class "Default")
      (node (ref "U3") (pin "8") (pinfunction "SENSOR_VN_8") (pintype "passive"))
    )
    (net (code "82") (name "unconnected-(U3-SENSOR_VP-Pad5)") (class "Default")
      (node (ref "U3") (pin "5") (pinfunction "SENSOR_VP_5") (pintype "passive"))
    )
    (net (code "83") (name "unconnected-(U3-VDD_SDIO_NC-Pad26)") (class "Default")
      (node (ref "U3") (pin "26") (pinfunction "VDD_SDIO_NC_26") (pintype "power_in"))
    )
    (net (code "84") (name "unconnected-(U3-XTAL_N_NC-Pad44)") (class "Default")
      (node (ref "U3") (pin "44") (pinfunction "XTAL_N_NC_44") (pintype "passive"))
    )
    (net (code "85") (name "unconnected-(U3-XTAL_P_NC-Pad45)") (class "Default")
      (node (ref "U3") (pin "45") (pinfunction "XTAL_P_NC_45") (pintype "passive"))
    )
    (net (code "86") (name "unconnected-(U5-GPIO1-Pad7)") (class "Default")
      (node (ref "U5") (pin "7") (pinfunction "GPIO1_7") (pintype "output+no_connect"))
    )
    (net (code "87") (name "unconnected-(U5-NC-Pad8)") (class "Default")
      (node (ref "U5") (pin "8") (pinfunction "NC_8") (pintype "passive+no_connect"))
    )
    (net (code "88") (name "unconnected-(U8-NC-Pad3)") (class "Default")
      (node (ref "U8") (pin "3") (pinfunction "NC_3") (pintype "passive"))
    )
    (net (code "89") (name "unconnected-(U8-NC-Pad4)") (class "Default")
      (node (ref "U8") (pin "4") (pinfunction "NC_4") (pintype "passive"))
    )
    (net (code "90") (name "unconnected-(X1-NC-Pad1)") (class "Default")
      (node (ref "X1") (pin "1") (pinfunction "NC_1") (pintype "passive+no_connect"))
    )
    (net (code "91") (name "unconnected-(X1-NC-Pad2)") (class "Default")
      (node (ref "X1") (pin "2") (pinfunction "NC_2") (pintype "passive+no_connect"))
    )
    (net (code "92") (name "unconnected-(X1-NC-Pad9)") (class "Default")
      (node (ref "X1") (pin "9") (pinfunction "NC_9") (pintype "passive+no_connect"))
    )
  )
)
